# MIXER.net
KiCad netlist of a schematic drawn in Altium Designer
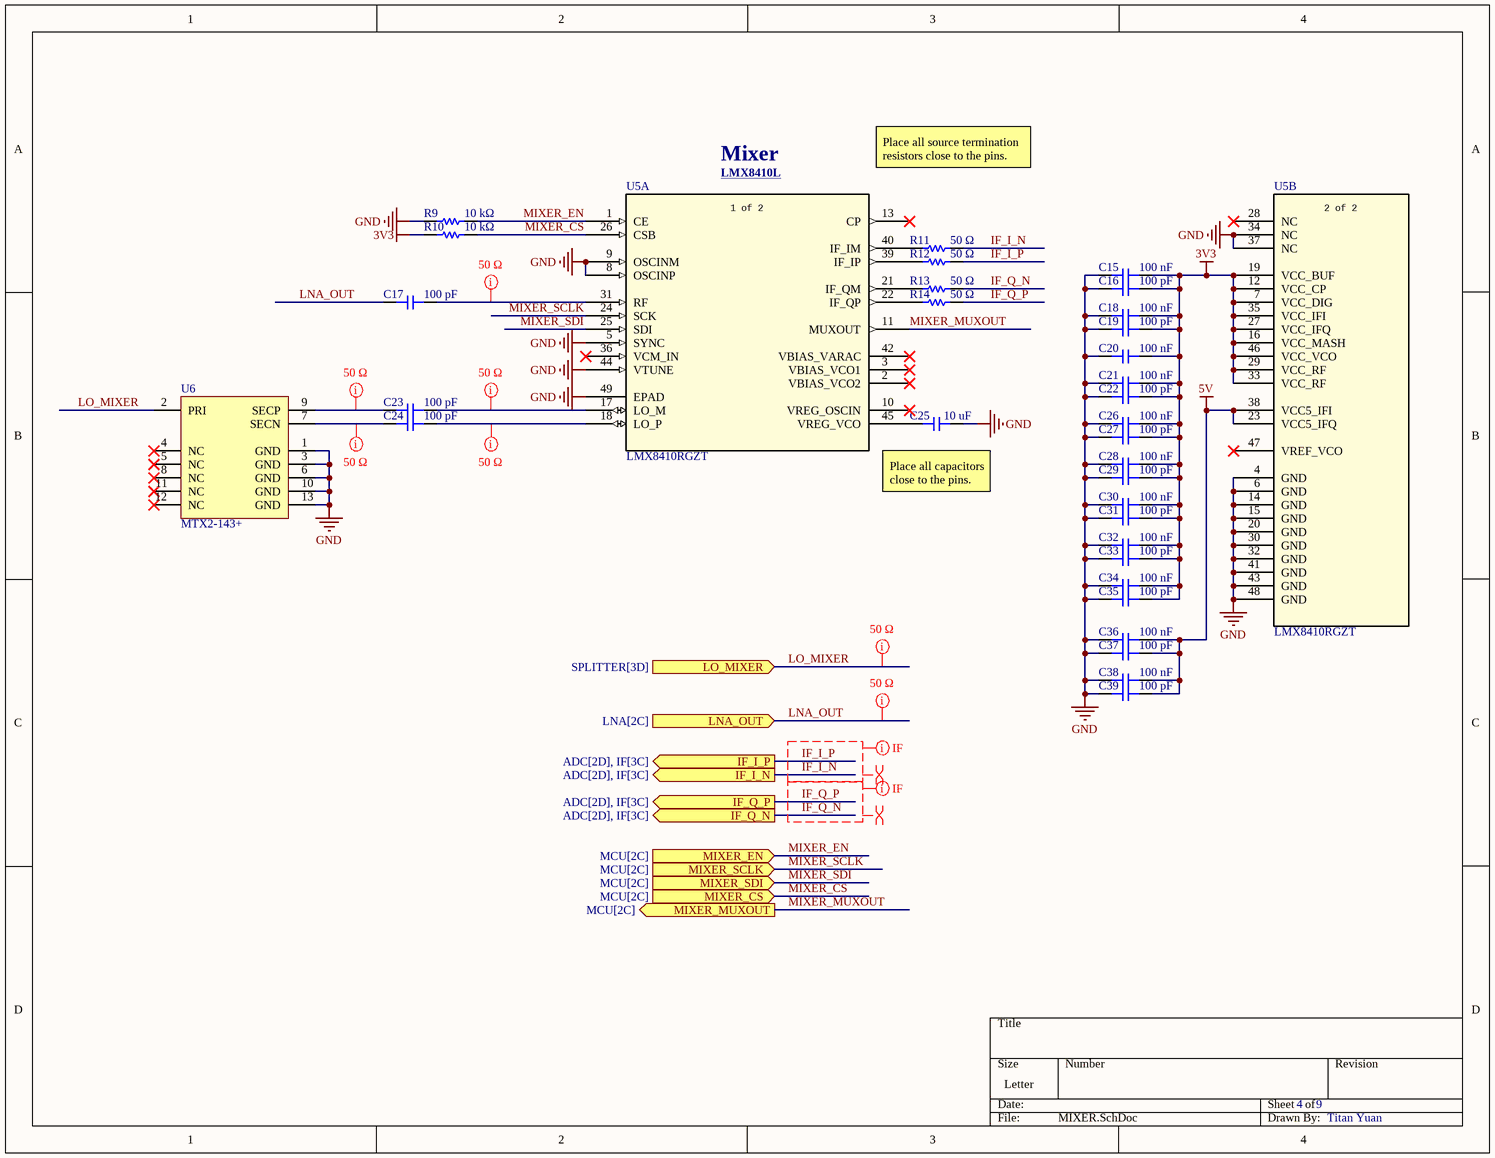
[diagram p0: MIXER.SchDoc]

(export (version "E")
  (design (tool "Eeschema 10.0.6"))
  (components
    (comp (ref "C15")
      (value "100 nF")
      (footprint "CAP_0402")
      (description "Ceramic Capacitor, Ceramic, 50V, 10% +Tol, 10% -Tol, X7R, 15% TC, 0.1uF, Surface Mount, 0402")
      (fields
        (field (name "MANUFACTURER") "Yageo")
        (field (name "MANUFACTURER PART NUMBER") "CC0402KPX7R9BB104")
      )
      (libsource (lib "Titan") (part "CAP"))
    )
    (comp (ref "C16")
      (value "100 pF")
      (footprint "CAP_0402")
      (description "50V 100pF NP0 ±5% 0402 Multilayer Ceramic Capacitors MLCC - SMD/SMT ROHS")
      (fields
        (field (name "MANUFACTURER") "Yageo")
        (field (name "MANUFACTURER PART NUMBER") "CC0402JRNPO9BN101")
      )
      (libsource (lib "Titan") (part "CAP"))
    )
    (comp (ref "C17")
      (value "100 pF")
      (footprint "CAP_0402")
      (description "50V 100pF NP0 ±5% 0402 Multilayer Ceramic Capacitors MLCC - SMD/SMT ROHS")
      (fields
        (field (name "MANUFACTURER") "Yageo")
        (field (name "MANUFACTURER PART NUMBER") "CC0402JRNPO9BN101")
      )
      (libsource (lib "Titan") (part "CAP"))
    )
    (comp (ref "C18")
      (value "100 nF")
      (footprint "CAP_0402")
      (description "Ceramic Capacitor, Ceramic, 50V, 10% +Tol, 10% -Tol, X7R, 15% TC, 0.1uF, Surface Mount, 0402")
      (fields
        (field (name "MANUFACTURER") "Yageo")
        (field (name "MANUFACTURER PART NUMBER") "CC0402KPX7R9BB104")
      )
      (libsource (lib "Titan") (part "CAP"))
    )
    (comp (ref "C19")
      (value "100 pF")
      (footprint "CAP_0402")
      (description "50V 100pF NP0 ±5% 0402 Multilayer Ceramic Capacitors MLCC - SMD/SMT ROHS")
      (fields
        (field (name "MANUFACTURER") "Yageo")
        (field (name "MANUFACTURER PART NUMBER") "CC0402JRNPO9BN101")
      )
      (libsource (lib "Titan") (part "CAP"))
    )
    (comp (ref "C20")
      (value "100 nF")
      (footprint "CAP_0402")
      (description "Ceramic Capacitor, Ceramic, 50V, 10% +Tol, 10% -Tol, X7R, 15% TC, 0.1uF, Surface Mount, 0402")
      (fields
        (field (name "MANUFACTURER") "Yageo")
        (field (name "MANUFACTURER PART NUMBER") "CC0402KPX7R9BB104")
      )
      (libsource (lib "Titan") (part "CAP"))
    )
    (comp (ref "C21")
      (value "100 nF")
      (footprint "CAP_0402")
      (description "Ceramic Capacitor, Ceramic, 50V, 10% +Tol, 10% -Tol, X7R, 15% TC, 0.1uF, Surface Mount, 0402")
      (fields
        (field (name "MANUFACTURER") "Yageo")
        (field (name "MANUFACTURER PART NUMBER") "CC0402KPX7R9BB104")
      )
      (libsource (lib "Titan") (part "CAP"))
    )
    (comp (ref "C22")
      (value "100 pF")
      (footprint "CAP_0402")
      (description "50V 100pF NP0 ±5% 0402 Multilayer Ceramic Capacitors MLCC - SMD/SMT ROHS")
      (fields
        (field (name "MANUFACTURER") "Yageo")
        (field (name "MANUFACTURER PART NUMBER") "CC0402JRNPO9BN101")
      )
      (libsource (lib "Titan") (part "CAP"))
    )
    (comp (ref "C23")
      (value "100 pF")
      (footprint "CAP_0402")
      (description "50V 100pF NP0 ±5% 0402 Multilayer Ceramic Capacitors MLCC - SMD/SMT ROHS")
      (fields
        (field (name "MANUFACTURER") "Yageo")
        (field (name "MANUFACTURER PART NUMBER") "CC0402JRNPO9BN101")
      )
      (libsource (lib "Titan") (part "CAP"))
    )
    (comp (ref "C24")
      (value "100 pF")
      (footprint "CAP_0402")
      (description "50V 100pF NP0 ±5% 0402 Multilayer Ceramic Capacitors MLCC - SMD/SMT ROHS")
      (fields
        (field (name "MANUFACTURER") "Yageo")
        (field (name "MANUFACTURER PART NUMBER") "CC0402JRNPO9BN101")
      )
      (libsource (lib "Titan") (part "CAP"))
    )
    (comp (ref "C25")
      (value "10 uF")
      (footprint "CAP_0603")
      (description "10V 10uF X7R ±10% 0603 Multilayer Ceramic Capacitors MLCC - SMD/SMT ROHS")
      (fields
        (field (name "MANUFACTURER") "Murata Electronics")
        (field (name "MANUFACTURER PART NUMBER") "GRM188Z71A106KA73D")
      )
      (libsource (lib "Titan") (part "CAP"))
    )
    (comp (ref "C26")
      (value "100 nF")
      (footprint "CAP_0402")
      (description "Ceramic Capacitor, Ceramic, 50V, 10% +Tol, 10% -Tol, X7R, 15% TC, 0.1uF, Surface Mount, 0402")
      (fields
        (field (name "MANUFACTURER") "Yageo")
        (field (name "MANUFACTURER PART NUMBER") "CC0402KPX7R9BB104")
      )
      (libsource (lib "Titan") (part "CAP"))
    )
    (comp (ref "C27")
      (value "100 pF")
      (footprint "CAP_0402")
      (description "50V 100pF NP0 ±5% 0402 Multilayer Ceramic Capacitors MLCC - SMD/SMT ROHS")
      (fields
        (field (name "MANUFACTURER") "Yageo")
        (field (name "MANUFACTURER PART NUMBER") "CC0402JRNPO9BN101")
      )
      (libsource (lib "Titan") (part "CAP"))
    )
    (comp (ref "C28")
      (value "100 nF")
      (footprint "CAP_0402")
      (description "Ceramic Capacitor, Ceramic, 50V, 10% +Tol, 10% -Tol, X7R, 15% TC, 0.1uF, Surface Mount, 0402")
      (fields
        (field (name "MANUFACTURER") "Yageo")
        (field (name "MANUFACTURER PART NUMBER") "CC0402KPX7R9BB104")
      )
      (libsource (lib "Titan") (part "CAP"))
    )
    (comp (ref "C29")
      (value "100 pF")
      (footprint "CAP_0402")
      (description "50V 100pF NP0 ±5% 0402 Multilayer Ceramic Capacitors MLCC - SMD/SMT ROHS")
      (fields
        (field (name "MANUFACTURER") "Yageo")
        (field (name "MANUFACTURER PART NUMBER") "CC0402JRNPO9BN101")
      )
      (libsource (lib "Titan") (part "CAP"))
    )
    (comp (ref "C30")
      (value "100 nF")
      (footprint "CAP_0402")
      (description "Ceramic Capacitor, Ceramic, 50V, 10% +Tol, 10% -Tol, X7R, 15% TC, 0.1uF, Surface Mount, 0402")
      (fields
        (field (name "MANUFACTURER") "Yageo")
        (field (name "MANUFACTURER PART NUMBER") "CC0402KPX7R9BB104")
      )
      (libsource (lib "Titan") (part "CAP"))
    )
    (comp (ref "C31")
      (value "100 pF")
      (footprint "CAP_0402")
      (description "50V 100pF NP0 ±5% 0402 Multilayer Ceramic Capacitors MLCC - SMD/SMT ROHS")
      (fields
        (field (name "MANUFACTURER") "Yageo")
        (field (name "MANUFACTURER PART NUMBER") "CC0402JRNPO9BN101")
      )
      (libsource (lib "Titan") (part "CAP"))
    )
    (comp (ref "C32")
      (value "100 nF")
      (footprint "CAP_0402")
      (description "Ceramic Capacitor, Ceramic, 50V, 10% +Tol, 10% -Tol, X7R, 15% TC, 0.1uF, Surface Mount, 0402")
      (fields
        (field (name "MANUFACTURER") "Yageo")
        (field (name "MANUFACTURER PART NUMBER") "CC0402KPX7R9BB104")
      )
      (libsource (lib "Titan") (part "CAP"))
    )
    (comp (ref "C33")
      (value "100 pF")
      (footprint "CAP_0402")
      (description "50V 100pF NP0 ±5% 0402 Multilayer Ceramic Capacitors MLCC - SMD/SMT ROHS")
      (fields
        (field (name "MANUFACTURER") "Yageo")
        (field (name "MANUFACTURER PART NUMBER") "CC0402JRNPO9BN101")
      )
      (libsource (lib "Titan") (part "CAP"))
    )
    (comp (ref "C34")
      (value "100 nF")
      (footprint "CAP_0402")
      (description "Ceramic Capacitor, Ceramic, 50V, 10% +Tol, 10% -Tol, X7R, 15% TC, 0.1uF, Surface Mount, 0402")
      (fields
        (field (name "MANUFACTURER") "Yageo")
        (field (name "MANUFACTURER PART NUMBER") "CC0402KPX7R9BB104")
      )
      (libsource (lib "Titan") (part "CAP"))
    )
    (comp (ref "C35")
      (value "100 pF")
      (footprint "CAP_0402")
      (description "50V 100pF NP0 ±5% 0402 Multilayer Ceramic Capacitors MLCC - SMD/SMT ROHS")
      (fields
        (field (name "MANUFACTURER") "Yageo")
        (field (name "MANUFACTURER PART NUMBER") "CC0402JRNPO9BN101")
      )
      (libsource (lib "Titan") (part "CAP"))
    )
    (comp (ref "C36")
      (value "100 nF")
      (footprint "CAP_0402")
      (description "Ceramic Capacitor, Ceramic, 50V, 10% +Tol, 10% -Tol, X7R, 15% TC, 0.1uF, Surface Mount, 0402")
      (fields
        (field (name "MANUFACTURER") "Yageo")
        (field (name "MANUFACTURER PART NUMBER") "CC0402KPX7R9BB104")
      )
      (libsource (lib "Titan") (part "CAP"))
    )
    (comp (ref "C37")
      (value "100 pF")
      (footprint "CAP_0402")
      (description "50V 100pF NP0 ±5% 0402 Multilayer Ceramic Capacitors MLCC - SMD/SMT ROHS")
      (fields
        (field (name "MANUFACTURER") "Yageo")
        (field (name "MANUFACTURER PART NUMBER") "CC0402JRNPO9BN101")
      )
      (libsource (lib "Titan") (part "CAP"))
    )
    (comp (ref "C38")
      (value "100 nF")
      (footprint "CAP_0402")
      (description "Ceramic Capacitor, Ceramic, 50V, 10% +Tol, 10% -Tol, X7R, 15% TC, 0.1uF, Surface Mount, 0402")
      (fields
        (field (name "MANUFACTURER") "Yageo")
        (field (name "MANUFACTURER PART NUMBER") "CC0402KPX7R9BB104")
      )
      (libsource (lib "Titan") (part "CAP"))
    )
    (comp (ref "C39")
      (value "100 pF")
      (footprint "CAP_0402")
      (description "50V 100pF NP0 ±5% 0402 Multilayer Ceramic Capacitors MLCC - SMD/SMT ROHS")
      (fields
        (field (name "MANUFACTURER") "Yageo")
        (field (name "MANUFACTURER PART NUMBER") "CC0402JRNPO9BN101")
      )
      (libsource (lib "Titan") (part "CAP"))
    )
    (comp (ref "R9")
      (value "10 kΩ")
      (footprint "RES_0402")
      (description "Res Thick Film 0402 10K Ohm 1% 0.063W(1/16W) ±100ppm/C Pad SMD T/R")
      (fields
        (field (name "MANUFACTURER") "Yageo")
        (field (name "MANUFACTURER PART NUMBER") "RC0402FR-0710KL")
      )
      (libsource (lib "Titan") (part "RES"))
    )
    (comp (ref "R10")
      (value "10 kΩ")
      (footprint "RES_0402")
      (description "Res Thick Film 0402 10K Ohm 1% 0.063W(1/16W) ±100ppm/C Pad SMD T/R")
      (fields
        (field (name "MANUFACTURER") "Yageo")
        (field (name "MANUFACTURER PART NUMBER") "RC0402FR-0710KL")
      )
      (libsource (lib "Titan") (part "RES"))
    )
    (comp (ref "R11")
      (value "50 Ω")
      (footprint "RES_0402")
      (description "62.5mW Thin Film Resistor ±50ppm/℃ ±0.1% 50Ω 0402 Chip Resistor - Surface Mount ROHS")
      (fields
        (field (name "MANUFACTURER") "Yageo")
        (field (name "MANUFACTURER PART NUMBER") "RT0402BRE0750RL")
      )
      (libsource (lib "Titan") (part "RES"))
    )
    (comp (ref "R12")
      (value "50 Ω")
      (footprint "RES_0402")
      (description "62.5mW Thin Film Resistor ±50ppm/℃ ±0.1% 50Ω 0402 Chip Resistor - Surface Mount ROHS")
      (fields
        (field (name "MANUFACTURER") "Yageo")
        (field (name "MANUFACTURER PART NUMBER") "RT0402BRE0750RL")
      )
      (libsource (lib "Titan") (part "RES"))
    )
    (comp (ref "R13")
      (value "50 Ω")
      (footprint "RES_0402")
      (description "62.5mW Thin Film Resistor ±50ppm/℃ ±0.1% 50Ω 0402 Chip Resistor - Surface Mount ROHS")
      (fields
        (field (name "MANUFACTURER") "Yageo")
        (field (name "MANUFACTURER PART NUMBER") "RT0402BRE0750RL")
      )
      (libsource (lib "Titan") (part "RES"))
    )
    (comp (ref "R14")
      (value "50 Ω")
      (footprint "RES_0402")
      (description "62.5mW Thin Film Resistor ±50ppm/℃ ±0.1% 50Ω 0402 Chip Resistor - Surface Mount ROHS")
      (fields
        (field (name "MANUFACTURER") "Yageo")
        (field (name "MANUFACTURER PART NUMBER") "RT0402BRE0750RL")
      )
      (libsource (lib "Titan") (part "RES"))
    )
    (comp (ref "U5")
      (value "LMX8410RGZT")
      (footprint "RGZ48_TEX")
      (description "High-Performance Mixer With Integrated Synthesizer 48-VQFN -40 to 85")
      (fields
        (field (name "MANUFACTURER") "Texas Instruments")
        (field (name "COPYRIGHT") "Copyright (C) 2026 Ultra Librarian. All rights reserved.")
      )
      (libsource (lib "LMX8410RGZT") (part "LMX8410RGZT"))
    )
    (comp (ref "U6")
      (value "MTX2-143+")
      (footprint "PL-497")
      (description "RF Transformer, 5500MHz Min")
      (fields (field (name "MANUFACTURER") "Mini-Circuits"))
      (libsource (lib "Titan") (part "MTX2-143+"))
    )
  )
  (nets
    (net (code "1") (name "/IF_I_N") (class "Default") (node (ref "R11") (pin "1") (pintype "passive")))
    (net (code "2") (name "/IF_I_P") (class "Default") (node (ref "R12") (pin "1") (pintype "passive")))
    (net (code "3") (name "/IF_Q_N") (class "Default") (node (ref "R13") (pin "1") (pintype "passive")))
    (net (code "4") (name "/IF_Q_P") (class "Default") (node (ref "R14") (pin "1") (pintype "passive")))
    (net (code "5") (name "/LNA_OUT") (class "Default") (node (ref "C17") (pin "2") (pintype "passive")))
    (net (code "6") (name "/LO_MIXER") (class "Default")
      (node (ref "U6") (pin "2") (pinfunction "PRI_2") (pintype "passive"))
    )
    (net (code "7") (name "/MIXER_CS") (class "Default")
      (node (ref "R10") (pin "1") (pintype "passive"))
      (node (ref "U5") (pin "26") (pinfunction "CSB_26") (pintype "input"))
    )
    (net (code "8") (name "/MIXER_EN") (class "Default")
      (node (ref "R9") (pin "1") (pintype "passive"))
      (node (ref "U5") (pin "1") (pinfunction "CE_1") (pintype "input"))
    )
    (net (code "9") (name "/MIXER_MUXOUT") (class "Default")
      (node (ref "U5") (pin "11") (pinfunction "MUXOUT_11") (pintype "output"))
    )
    (net (code "10") (name "/MIXER_SCLK") (class "Default")
      (node (ref "U5") (pin "24") (pinfunction "SCK_24") (pintype "input"))
    )
    (net (code "11") (name "/MIXER_SDI") (class "Default")
      (node (ref "U5") (pin "25") (pinfunction "SDI_25") (pintype "input"))
    )
    (net (code "12") (name "3V3") (class "Default")
      (node (ref "C15") (pin "2") (pintype "passive"))
      (node (ref "C16") (pin "1") (pintype "passive"))
      (node (ref "C18") (pin "2") (pintype "passive"))
      (node (ref "C19") (pin "1") (pintype "passive"))
      (node (ref "C20") (pin "2") (pintype "passive"))
      (node (ref "C21") (pin "2") (pintype "passive"))
      (node (ref "C22") (pin "1") (pintype "passive"))
      (node (ref "C26") (pin "2") (pintype "passive"))
      (node (ref "C27") (pin "1") (pintype "passive"))
      (node (ref "C28") (pin "2") (pintype "passive"))
      (node (ref "C29") (pin "1") (pintype "passive"))
      (node (ref "C30") (pin "2") (pintype "passive"))
      (node (ref "C31") (pin "1") (pintype "passive"))
      (node (ref "C32") (pin "2") (pintype "passive"))
      (node (ref "C33") (pin "1") (pintype "passive"))
      (node (ref "C34") (pin "2") (pintype "passive"))
      (node (ref "C35") (pin "1") (pintype "passive"))
      (node (ref "R10") (pin "2") (pintype "passive"))
      (node (ref "U5") (pin "12") (pinfunction "VCC_CP_12") (pintype "power_in"))
      (node (ref "U5") (pin "16") (pinfunction "VCC_MASH_16") (pintype "power_in"))
      (node (ref "U5") (pin "19") (pinfunction "VCC_BUF_19") (pintype "power_in"))
      (node (ref "U5") (pin "27") (pinfunction "VCC_IFQ_27") (pintype "power_in"))
      (node (ref "U5") (pin "29") (pinfunction "VCC_RF_29") (pintype "power_in"))
      (node (ref "U5") (pin "33") (pinfunction "VCC_RF_33") (pintype "power_in"))
      (node (ref "U5") (pin "35") (pinfunction "VCC_IFI_35") (pintype "power_in"))
      (node (ref "U5") (pin "46") (pinfunction "VCC_VCO_46") (pintype "power_in"))
      (node (ref "U5") (pin "7") (pinfunction "VCC_DIG_7") (pintype "power_in"))
    )
    (net (code "13") (name "5V") (class "Default")
      (node (ref "C36") (pin "2") (pintype "passive"))
      (node (ref "C37") (pin "1") (pintype "passive"))
      (node (ref "C38") (pin "2") (pintype "passive"))
      (node (ref "C39") (pin "1") (pintype "passive"))
      (node (ref "U5") (pin "23") (pinfunction "VCC5_IFQ_23") (pintype "power_in"))
      (node (ref "U5") (pin "38") (pinfunction "VCC5_IFI_38") (pintype "power_in"))
    )
    (net (code "14") (name "GND") (class "Default")
      (node (ref "C15") (pin "1") (pintype "passive"))
      (node (ref "C16") (pin "2") (pintype "passive"))
      (node (ref "C18") (pin "1") (pintype "passive"))
      (node (ref "C19") (pin "2") (pintype "passive"))
      (node (ref "C20") (pin "1") (pintype "passive"))
      (node (ref "C21") (pin "1") (pintype "passive"))
      (node (ref "C22") (pin "2") (pintype "passive"))
      (node (ref "C25") (pin "1") (pintype "passive"))
      (node (ref "C26") (pin "1") (pintype "passive"))
      (node (ref "C27") (pin "2") (pintype "passive"))
      (node (ref "C28") (pin "1") (pintype "passive"))
      (node (ref "C29") (pin "2") (pintype "passive"))
      (node (ref "C30") (pin "1") (pintype "passive"))
      (node (ref "C31") (pin "2") (pintype "passive"))
      (node (ref "C32") (pin "1") (pintype "passive"))
      (node (ref "C33") (pin "2") (pintype "passive"))
      (node (ref "C34") (pin "1") (pintype "passive"))
      (node (ref "C35") (pin "2") (pintype "passive"))
      (node (ref "C36") (pin "1") (pintype "passive"))
      (node (ref "C37") (pin "2") (pintype "passive"))
      (node (ref "C38") (pin "1") (pintype "passive"))
      (node (ref "C39") (pin "2") (pintype "passive"))
      (node (ref "R9") (pin "2") (pintype "passive"))
      (node (ref "U5") (pin "14") (pinfunction "GND_14") (pintype "power_in"))
      (node (ref "U5") (pin "15") (pinfunction "GND_15") (pintype "power_in"))
      (node (ref "U5") (pin "20") (pinfunction "GND_20") (pintype "power_in"))
      (node (ref "U5") (pin "30") (pinfunction "GND_30") (pintype "power_in"))
      (node (ref "U5") (pin "32") (pinfunction "GND_32") (pintype "power_in"))
      (node (ref "U5") (pin "34") (pinfunction "NC_34") (pintype "power_in"))
      (node (ref "U5") (pin "37") (pinfunction "NC_37") (pintype "passive"))
      (node (ref "U5") (pin "4") (pinfunction "GND_4") (pintype "power_in"))
      (node (ref "U5") (pin "41") (pinfunction "GND_41") (pintype "power_in"))
      (node (ref "U5") (pin "43") (pinfunction "GND_43") (pintype "power_in"))
      (node (ref "U5") (pin "44") (pinfunction "VTUNE_44") (pintype "input"))
      (node (ref "U5") (pin "48") (pinfunction "GND_48") (pintype "power_in"))
      (node (ref "U5") (pin "49") (pinfunction "EPAD_49") (pintype "passive"))
      (node (ref "U5") (pin "5") (pinfunction "SYNC_5") (pintype "input"))
      (node (ref "U5") (pin "6") (pinfunction "GND_6") (pintype "power_in"))
      (node (ref "U5") (pin "8") (pinfunction "OSCINP_8") (pintype "input"))
      (node (ref "U5") (pin "9") (pinfunction "OSCINM_9") (pintype "input"))
      (node (ref "U6") (pin "1") (pinfunction "GND_1") (pintype "power_in"))
      (node (ref "U6") (pin "10") (pinfunction "GND_10") (pintype "power_in"))
      (node (ref "U6") (pin "13") (pinfunction "GND_13") (pintype "power_in"))
      (node (ref "U6") (pin "3") (pinfunction "GND_3") (pintype "power_in"))
      (node (ref "U6") (pin "6") (pinfunction "GND_6") (pintype "power_in"))
    )
    (net (code "15") (name "Net-(U5A-IF_IM)") (class "Default")
      (node (ref "R11") (pin "2") (pintype "passive"))
      (node (ref "U5") (pin "40") (pinfunction "IF_IM_40") (pintype "output"))
    )
    (net (code "16") (name "Net-(U5A-IF_IP)") (class "Default")
      (node (ref "R12") (pin "2") (pintype "passive"))
      (node (ref "U5") (pin "39") (pinfunction "IF_IP_39") (pintype "output"))
    )
    (net (code "17") (name "Net-(U5A-IF_QM)") (class "Default")
      (node (ref "R13") (pin "2") (pintype "passive"))
      (node (ref "U5") (pin "21") (pinfunction "IF_QM_21") (pintype "output"))
    )
    (net (code "18") (name "Net-(U5A-IF_QP)") (class "Default")
      (node (ref "R14") (pin "2") (pintype "passive"))
      (node (ref "U5") (pin "22") (pinfunction "IF_QP_22") (pintype "output"))
    )
    (net (code "19") (name "Net-(U5A-LO_M)") (class "Default")
      (node (ref "C23") (pin "1") (pintype "passive"))
      (node (ref "U5") (pin "17") (pinfunction "LO_M_17") (pintype "bidirectional"))
    )
    (net (code "20") (name "Net-(U5A-LO_P)") (class "Default")
      (node (ref "C24") (pin "1") (pintype "passive"))
      (node (ref "U5") (pin "18") (pinfunction "LO_P_18") (pintype "bidirectional"))
    )
    (net (code "21") (name "Net-(U5A-RF)") (class "Default")
      (node (ref "C17") (pin "1") (pintype "passive"))
      (node (ref "U5") (pin "31") (pinfunction "RF_31") (pintype "input"))
    )
    (net (code "22") (name "Net-(U5A-VREG_VCO)") (class "Default")
      (node (ref "C25") (pin "2") (pintype "passive"))
      (node (ref "U5") (pin "45") (pinfunction "VREG_VCO_45") (pintype "passive"))
    )
    (net (code "23") (name "Net-(U6-SECN)") (class "Default")
      (node (ref "C24") (pin "2") (pintype "passive"))
      (node (ref "U6") (pin "7") (pinfunction "SECN_7") (pintype "passive"))
    )
    (net (code "24") (name "Net-(U6-SECP)") (class "Default")
      (node (ref "C23") (pin "2") (pintype "passive"))
      (node (ref "U6") (pin "9") (pinfunction "SECP_9") (pintype "passive"))
    )
    (net (code "25") (name "unconnected-(U5A-CP-Pad13)") (class "Default")
      (node (ref "U5") (pin "13") (pinfunction "CP_13") (pintype "output+no_connect"))
    )
    (net (code "26") (name "unconnected-(U5A-VBIAS_VARAC-Pad42)") (class "Default")
      (node (ref "U5") (pin "42") (pinfunction "VBIAS_VARAC_42") (pintype "passive+no_connect"))
    )
    (net (code "27") (name "unconnected-(U5A-VBIAS_VCO1-Pad3)") (class "Default")
      (node (ref "U5") (pin "3") (pinfunction "VBIAS_VCO1_3") (pintype "passive+no_connect"))
    )
    (net (code "28") (name "unconnected-(U5A-VBIAS_VCO2-Pad2)") (class "Default")
      (node (ref "U5") (pin "2") (pinfunction "VBIAS_VCO2_2") (pintype "passive+no_connect"))
    )
    (net (code "29") (name "unconnected-(U5A-VCM_IN-Pad36)") (class "Default")
      (node (ref "U5") (pin "36") (pinfunction "VCM_IN_36") (pintype "input+no_connect"))
    )
    (net (code "30") (name "unconnected-(U5A-VREG_OSCIN-Pad10)") (class "Default")
      (node (ref "U5") (pin "10") (pinfunction "VREG_OSCIN_10") (pintype "passive+no_connect"))
    )
    (net (code "31") (name "unconnected-(U5B-NC-Pad28)") (class "Default")
      (node (ref "U5") (pin "28") (pinfunction "NC_28") (pintype "passive+no_connect"))
    )
    (net (code "32") (name "unconnected-(U5B-VREF_VCO-Pad47)") (class "Default")
      (node (ref "U5") (pin "47") (pinfunction "VREF_VCO_47") (pintype "passive+no_connect"))
    )
    (net (code "33") (name "unconnected-(U6-NC-Pad4)") (class "Default")
      (node (ref "U6") (pin "4") (pinfunction "NC_4") (pintype "passive+no_connect"))
    )
    (net (code "34") (name "unconnected-(U6-NC-Pad5)") (class "Default")
      (node (ref "U6") (pin "5") (pinfunction "NC_5") (pintype "passive+no_connect"))
    )
    (net (code "35") (name "unconnected-(U6-NC-Pad8)") (class "Default")
      (node (ref "U6") (pin "8") (pinfunction "NC_8") (pintype "passive+no_connect"))
    )
    (net (code "36") (name "unconnected-(U6-NC-Pad11)") (class "Default")
      (node (ref "U6") (pin "11") (pinfunction "NC_11") (pintype "passive+no_connect"))
    )
    (net (code "37") (name "unconnected-(U6-NC-Pad12)") (class "Default")
      (node (ref "U6") (pin "12") (pinfunction "NC_12") (pintype "passive+no_connect"))
    )
  )
)
